# Addon-mapleCUx_HM-RFM69-V10-005.net
KiCad netlist of a schematic drawn in EAGLE
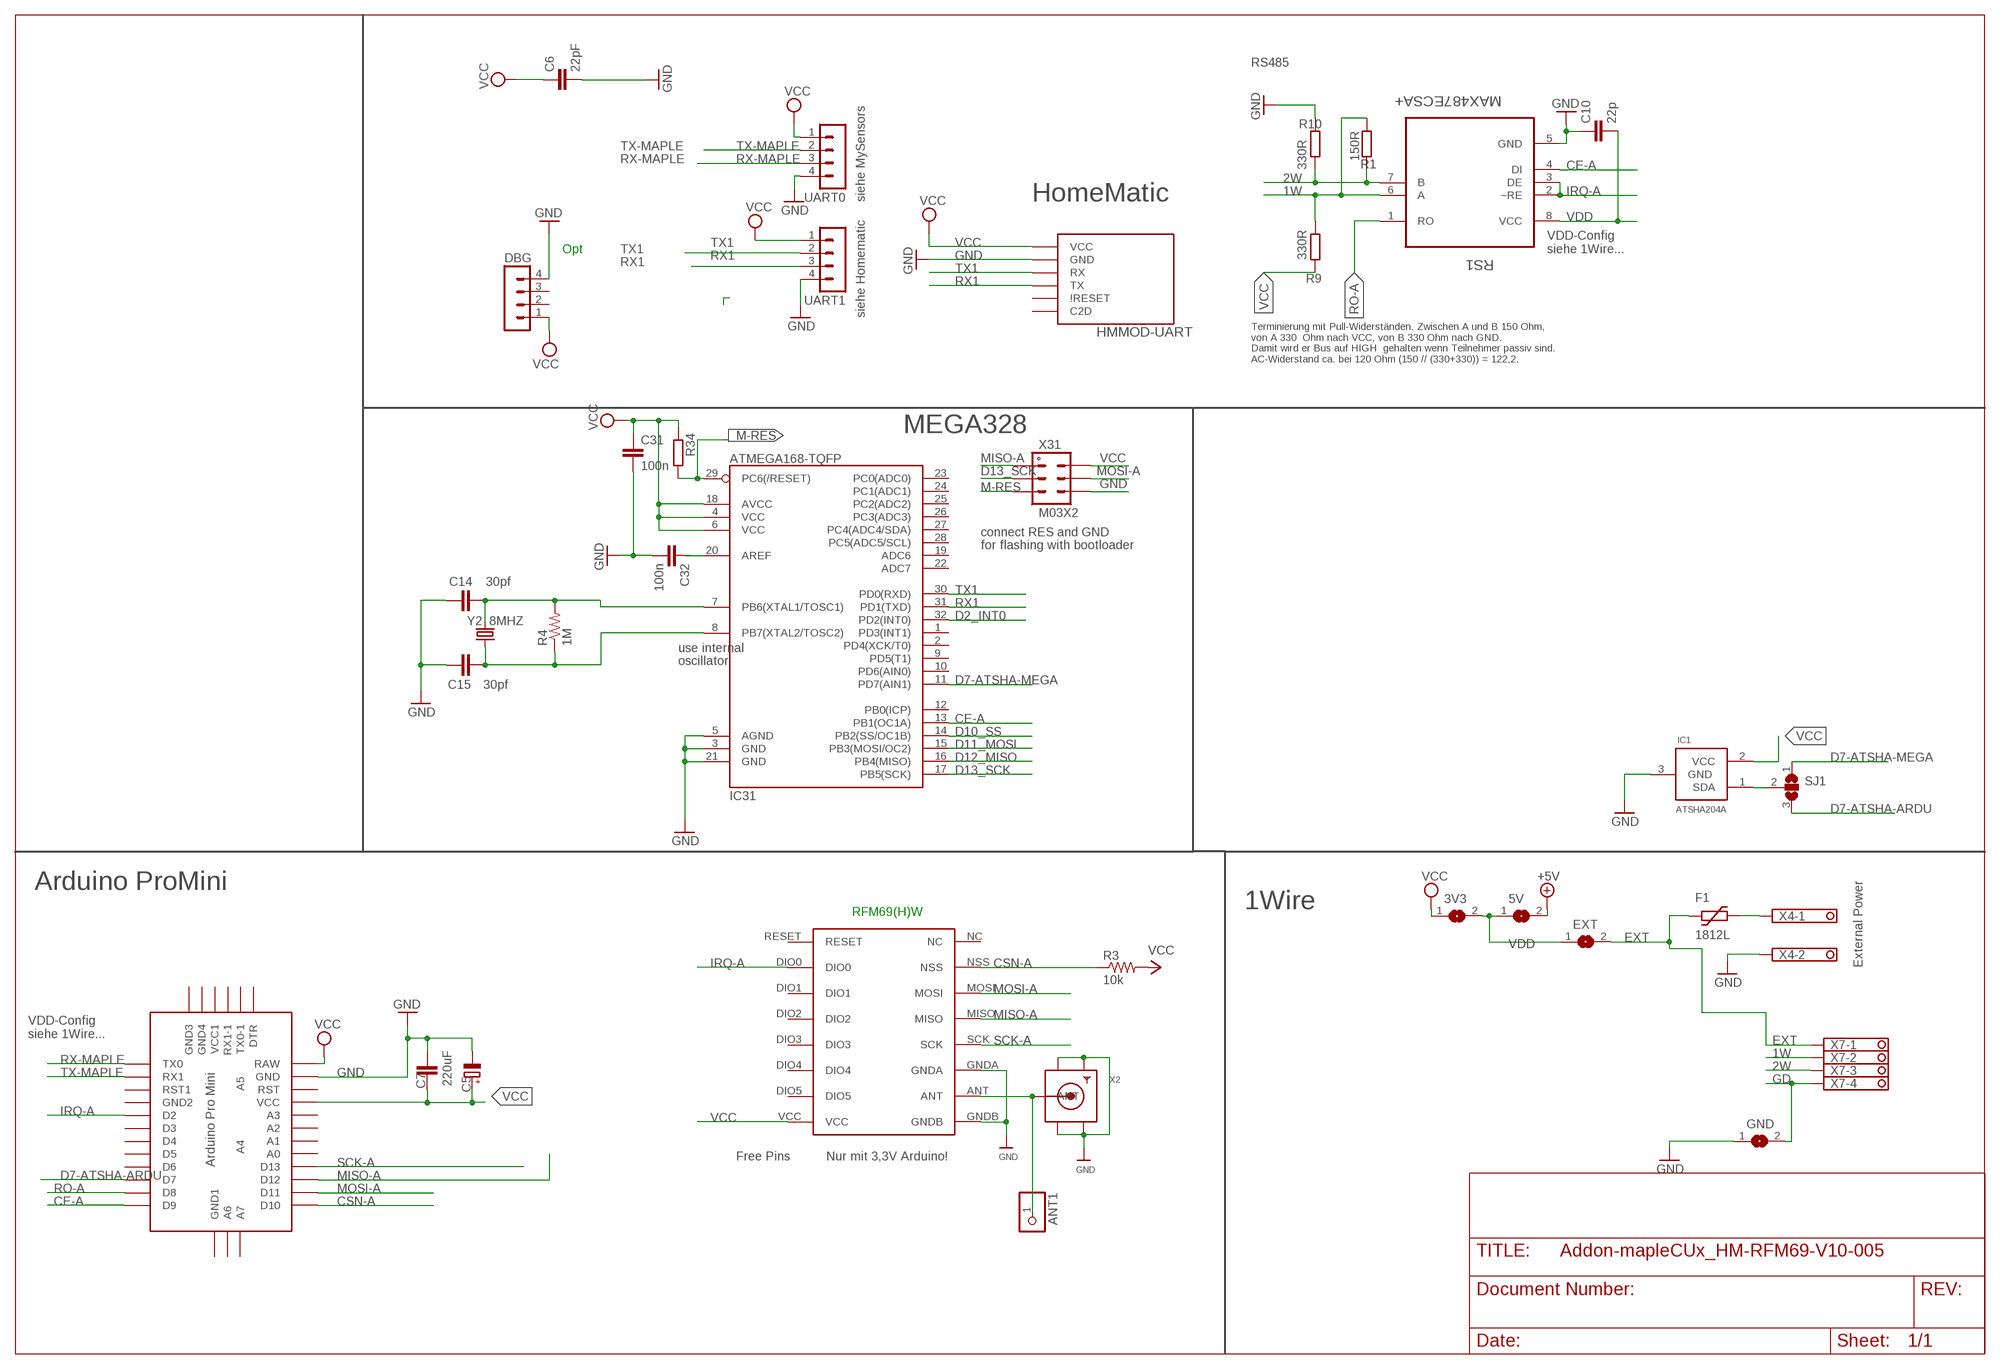
[diagram p0: schematic, sheet 1]

(export (version "E")
  (design (tool "Eeschema 10.0.6"))
  (components
    (comp (ref "3V3") (value "SJ") (footprint "eagle-import:SJ") (libsource (lib "eagle-import") (part "SJ")))
    (comp (ref "5V") (value "SJ") (footprint "eagle-import:SJ") (libsource (lib "eagle-import") (part "SJ")))
    (comp (ref "ANT1")
      (value "PINHD-1X1")
      (footprint "eagle-import:1X01")
      (libsource (lib "eagle-import") (part "PINHD-1X1"))
    )
    (comp (ref "C5")
      (value "220uF")
      (footprint "eagle-import:E5-8,5")
      (libsource (lib "eagle-import") (part "CPOL-EUE5-8.5"))
    )
    (comp (ref "C6")
      (value "22pF")
      (footprint "eagle-import:C0805")
      (libsource (lib "eagle-import") (part "C-EUC0805"))
    )
    (comp (ref "C7")
      (value "C-EUC1812")
      (footprint "eagle-import:C1812")
      (libsource (lib "eagle-import") (part "C-EUC1812"))
    )
    (comp (ref "C10")
      (value "22p")
      (footprint "eagle-import:C0805")
      (libsource (lib "eagle-import") (part "C-EUC0805"))
    )
    (comp (ref "C14")
      (value "30pf")
      (footprint "eagle-import:0805")
      (libsource (lib "eagle-import") (part "CAP0805"))
    )
    (comp (ref "C15")
      (value "30pf")
      (footprint "eagle-import:0805")
      (libsource (lib "eagle-import") (part "CAP0805"))
    )
    (comp (ref "C31")
      (value "100n")
      (footprint "eagle-import:C0805")
      (libsource (lib "eagle-import") (part "C-EUC0805"))
    )
    (comp (ref "C32")
      (value "100n")
      (footprint "eagle-import:C0805")
      (libsource (lib "eagle-import") (part "C-EUC0805"))
    )
    (comp (ref "DBG")
      (value "MA04-1")
      (footprint "eagle-import:MA04-1")
      (libsource (lib "eagle-import") (part "MA04-1"))
    )
    (comp (ref "EXT") (value "SJ") (footprint "eagle-import:SJ") (libsource (lib "eagle-import") (part "SJ")))
    (comp (ref "F1")
      (value "1812L")
      (footprint "eagle-import:1812L")
      (libsource (lib "eagle-import") (part "1812L"))
    )
    (comp (ref "GND") (value "SJ") (footprint "eagle-import:SJ") (libsource (lib "eagle-import") (part "SJ")))
    (comp (ref "HMMOD-UART")
      (value "HM-MOD-UARTDIL")
      (footprint "eagle-import:HM-MOD-UART-DIL")
      (libsource (lib "eagle-import") (part "HM-MOD-UARTDIL"))
    )
    (comp (ref "IC1")
      (value "ATSHA204A")
      (footprint "eagle-import:SOT23")
      (libsource (lib "eagle-import") (part "ATSHA204A"))
    )
    (comp (ref "IC31")
      (value "ATMEGA168-TQFP")
      (footprint "eagle-import:TQFP32-08")
      (libsource (lib "eagle-import") (part "ATMEGA168-TQFP"))
    )
    (comp (ref "R1")
      (value "150R")
      (footprint "eagle-import:R0805")
      (libsource (lib "eagle-import") (part "R-EU_R0805"))
    )
    (comp (ref "R3")
      (value "10k")
      (footprint "eagle-import:0805")
      (libsource (lib "eagle-import") (part "RESISTOR0805-RES"))
    )
    (comp (ref "R4")
      (value "1M")
      (footprint "eagle-import:0805")
      (libsource (lib "eagle-import") (part "RESISTOR0805-RES"))
    )
    (comp (ref "R9")
      (value "330R")
      (footprint "eagle-import:R0805")
      (libsource (lib "eagle-import") (part "R-EU_R0805"))
    )
    (comp (ref "R10")
      (value "330R")
      (footprint "eagle-import:R0805")
      (libsource (lib "eagle-import") (part "R-EU_R0805"))
    )
    (comp (ref "R34")
      (value "R-EU_R0805")
      (footprint "eagle-import:R0805")
      (libsource (lib "eagle-import") (part "R-EU_R0805"))
    )
    (comp (ref "RFM69W")
      (value "RFM69HW")
      (footprint "eagle-import:RFM")
      (libsource (lib "eagle-import") (part "RFM69HW"))
    )
    (comp (ref "RS1")
      (value "MAX487ECSA+")
      (footprint "eagle-import:SOIC127P600X175-8N")
      (libsource (lib "eagle-import") (part "MAX487ECSA+"))
    )
    (comp (ref "SJ1")
      (value "SJ2W")
      (footprint "eagle-import:SJ_2")
      (libsource (lib "eagle-import") (part "SJ2W"))
    )
    (comp (ref "U$2")
      (value "ABK-PRO-MINI")
      (footprint "eagle-import:ABK-PRO-MINI")
      (libsource (lib "eagle-import") (part "ABK-PRO-MINI"))
    )
    (comp (ref "UART0")
      (value "MA04-1")
      (footprint "eagle-import:MA04-1")
      (libsource (lib "eagle-import") (part "MA04-1"))
    )
    (comp (ref "UART1")
      (value "MA04-1")
      (footprint "eagle-import:MA04-1")
      (libsource (lib "eagle-import") (part "MA04-1"))
    )
    (comp (ref "X2")
      (value "SMACONNECTOR_EDGE")
      (footprint "eagle-import:SMA_EDGELAUNCH")
      (libsource (lib "eagle-import") (part "SMACONNECTOR_EDGE"))
    )
    (comp (ref "X4")
      (value "1751248")
      (footprint "eagle-import:1751248")
      (libsource (lib "eagle-import") (part "1751248"))
    )
    (comp (ref "X7")
      (value "1751264")
      (footprint "eagle-import:1751264")
      (libsource (lib "eagle-import") (part "1751264"))
    )
    (comp (ref "X31")
      (value "M03X2")
      (footprint "eagle-import:2X03-1.27MM_SMD")
      (libsource (lib "eagle-import") (part "M03X2"))
    )
    (comp (ref "Y2")
      (value "8MHZ")
      (footprint "eagle-import:CRYSTAL-TXC-7A")
      (libsource (lib "eagle-import") (part "CRYSTALTXC-7A"))
    )
  )
  (nets
    (net (code "1") (name "+5V") (class "Default")
      (node (ref "5V") (pin "2") (pinfunction "2_2") (pintype "passive"))
    )
    (net (code "2") (name "/1W") (class "Default")
      (node (ref "R1") (pin "1") (pinfunction "1_1") (pintype "passive"))
      (node (ref "R9") (pin "2") (pinfunction "2_2") (pintype "passive"))
      (node (ref "RS1") (pin "6") (pinfunction "A_6") (pintype "bidirectional"))
      (node (ref "X7") (pin "2") (pinfunction "K_2") (pintype "passive"))
    )
    (net (code "3") (name "/2W") (class "Default")
      (node (ref "R1") (pin "2") (pinfunction "2_2") (pintype "passive"))
      (node (ref "R10") (pin "1") (pinfunction "1_1") (pintype "passive"))
      (node (ref "RS1") (pin "7") (pinfunction "B_7") (pintype "bidirectional"))
      (node (ref "X7") (pin "3") (pinfunction "K_3") (pintype "passive"))
    )
    (net (code "4") (name "/CE-A") (class "Default")
      (node (ref "IC31") (pin "13") (pinfunction "PB1(OC1A)_13") (pintype "bidirectional"))
      (node (ref "RS1") (pin "4") (pinfunction "DI_4") (pintype "input"))
      (node (ref "U$2") (pin "D9") (pinfunction "D9_D9") (pintype "bidirectional"))
    )
    (net (code "5") (name "/CSN-A") (class "Default")
      (node (ref "R3") (pin "1") (pinfunction "1_1") (pintype "passive"))
      (node (ref "RFM69W") (pin "NSS") (pinfunction "NSS_NSS") (pintype "bidirectional"))
      (node (ref "U$2") (pin "D10") (pinfunction "D10_D10") (pintype "bidirectional"))
    )
    (net (code "6") (name "/D2_INT0") (class "Default")
      (node (ref "IC31") (pin "32") (pinfunction "PD2(INT0)_32") (pintype "bidirectional"))
    )
    (net (code "7") (name "/D7-ATSHA-ARDU") (class "Default")
      (node (ref "SJ1") (pin "3") (pinfunction "3_3") (pintype "passive"))
      (node (ref "U$2") (pin "D7") (pinfunction "D7_D7") (pintype "bidirectional"))
    )
    (net (code "8") (name "/D7-ATSHA-MEGA") (class "Default")
      (node (ref "IC31") (pin "11") (pinfunction "PD7(AIN1)_11") (pintype "bidirectional"))
      (node (ref "SJ1") (pin "1") (pinfunction "1_1") (pintype "passive"))
    )
    (net (code "9") (name "/D10_SS") (class "Default")
      (node (ref "IC31") (pin "14") (pinfunction "PB2(SS/OC1B)_14") (pintype "bidirectional"))
    )
    (net (code "10") (name "/D11_MOSI") (class "Default")
      (node (ref "IC31") (pin "15") (pinfunction "PB3(MOSI/OC2)_15") (pintype "bidirectional"))
    )
    (net (code "11") (name "/D12_MISO") (class "Default")
      (node (ref "IC31") (pin "16") (pinfunction "PB4(MISO)_16") (pintype "bidirectional"))
    )
    (net (code "12") (name "/D13_SCK") (class "Default")
      (node (ref "IC31") (pin "17") (pinfunction "PB5(SCK)_17") (pintype "bidirectional"))
      (node (ref "X31") (pin "P$3") (pinfunction "3_P$3") (pintype "passive"))
    )
    (net (code "13") (name "/EXT") (class "Default")
      (node (ref "EXT") (pin "2") (pinfunction "2_2") (pintype "passive"))
      (node (ref "F1") (pin "P$1") (pinfunction "1_P$1") (pintype "passive"))
      (node (ref "X7") (pin "1") (pinfunction "K_1") (pintype "passive"))
    )
    (net (code "14") (name "/GD") (class "Default")
      (node (ref "GND") (pin "2") (pinfunction "2_2") (pintype "passive"))
      (node (ref "X7") (pin "4") (pinfunction "K_4") (pintype "passive"))
    )
    (net (code "15") (name "/IRQ-A") (class "Default")
      (node (ref "RFM69W") (pin "DIO0") (pinfunction "DIO0_DIO0") (pintype "bidirectional"))
      (node (ref "RS1") (pin "2") (pinfunction "~{RE}_2") (pintype "input"))
      (node (ref "RS1") (pin "3") (pinfunction "DE_3") (pintype "input"))
      (node (ref "U$2") (pin "D2") (pinfunction "D2_D2") (pintype "bidirectional"))
    )
    (net (code "16") (name "/M-RES") (class "Default")
      (node (ref "IC31") (pin "29") (pinfunction "PC6(/RESET)_29") (pintype "bidirectional"))
      (node (ref "R34") (pin "2") (pinfunction "2_2") (pintype "passive"))
      (node (ref "X31") (pin "P$5") (pinfunction "5_P$5") (pintype "passive"))
    )
    (net (code "17") (name "/MISO-A") (class "Default")
      (node (ref "RFM69W") (pin "MISO") (pinfunction "MISO_MISO") (pintype "bidirectional"))
      (node (ref "U$2") (pin "D12") (pinfunction "D12_D12") (pintype "bidirectional"))
      (node (ref "X31") (pin "P$1") (pinfunction "1_P$1") (pintype "passive"))
    )
    (net (code "18") (name "/MOSI-A") (class "Default")
      (node (ref "RFM69W") (pin "MOSI") (pinfunction "MOSI_MOSI") (pintype "bidirectional"))
      (node (ref "U$2") (pin "D11") (pinfunction "D11_D11") (pintype "bidirectional"))
      (node (ref "X31") (pin "P$4") (pinfunction "4_P$4") (pintype "passive"))
    )
    (net (code "19") (name "/RX-MAPLE") (class "Default")
      (node (ref "U$2") (pin "TX0") (pinfunction "TX0_TX0") (pintype "bidirectional"))
      (node (ref "UART0") (pin "3") (pinfunction "3_3") (pintype "passive"))
    )
    (net (code "20") (name "/RX1") (class "Default")
      (node (ref "HMMOD-UART") (pin "5") (pinfunction "TX_5") (pintype "bidirectional"))
      (node (ref "IC31") (pin "31") (pinfunction "PD1(TXD)_31") (pintype "bidirectional"))
      (node (ref "UART1") (pin "3") (pinfunction "3_3") (pintype "passive"))
    )
    (net (code "21") (name "/SCK-A") (class "Default")
      (node (ref "RFM69W") (pin "SCK") (pinfunction "SCK_SCK") (pintype "bidirectional"))
      (node (ref "U$2") (pin "D13") (pinfunction "D13_D13") (pintype "bidirectional"))
    )
    (net (code "22") (name "/TX-MAPLE") (class "Default")
      (node (ref "U$2") (pin "RX1") (pinfunction "RX1_RX1") (pintype "bidirectional"))
      (node (ref "UART0") (pin "2") (pinfunction "2_2") (pintype "passive"))
    )
    (net (code "23") (name "/TX1") (class "Default")
      (node (ref "HMMOD-UART") (pin "6") (pinfunction "RX_6") (pintype "bidirectional"))
      (node (ref "IC31") (pin "30") (pinfunction "PD0(RXD)_30") (pintype "bidirectional"))
      (node (ref "UART1") (pin "2") (pinfunction "2_2") (pintype "passive"))
    )
    (net (code "24") (name "/VDD") (class "Default")
      (node (ref "3V3") (pin "2") (pinfunction "2_2") (pintype "passive"))
      (node (ref "5V") (pin "1") (pinfunction "1_1") (pintype "passive"))
      (node (ref "C10") (pin "2") (pinfunction "2_2") (pintype "passive"))
      (node (ref "EXT") (pin "1") (pinfunction "1_1") (pintype "passive"))
      (node (ref "RS1") (pin "8") (pinfunction "VCC_8") (pintype "power_in"))
    )
    (net (code "25") (name "GND") (class "Default")
      (node (ref "C10") (pin "1") (pinfunction "1_1") (pintype "passive"))
      (node (ref "C14") (pin "1") (pinfunction "1_1") (pintype "passive"))
      (node (ref "C15") (pin "1") (pinfunction "1_1") (pintype "passive"))
      (node (ref "C31") (pin "2") (pinfunction "2_2") (pintype "passive"))
      (node (ref "C32") (pin "2") (pinfunction "2_2") (pintype "passive"))
      (node (ref "C5") (pin "-") (pinfunction "-_-") (pintype "passive"))
      (node (ref "C6") (pin "2") (pinfunction "2_2") (pintype "passive"))
      (node (ref "C7") (pin "1") (pinfunction "1_1") (pintype "passive"))
      (node (ref "DBG") (pin "4") (pinfunction "4_4") (pintype "passive"))
      (node (ref "GND") (pin "1") (pinfunction "1_1") (pintype "passive"))
      (node (ref "HMMOD-UART") (pin "2") (pinfunction "GND_2") (pintype "power_in"))
      (node (ref "IC1") (pin "3") (pinfunction "GND_3") (pintype "bidirectional"))
      (node (ref "IC31") (pin "21") (pinfunction "GND_21") (pintype "bidirectional"))
      (node (ref "IC31") (pin "3") (pinfunction "GND_3") (pintype "bidirectional"))
      (node (ref "IC31") (pin "5") (pinfunction "AGND_5") (pintype "bidirectional"))
      (node (ref "R10") (pin "2") (pinfunction "2_2") (pintype "passive"))
      (node (ref "RFM69W") (pin "GNDA") (pinfunction "GNDA_GNDA") (pintype "bidirectional"))
      (node (ref "RFM69W") (pin "GNDB") (pinfunction "GNDB_GNDB") (pintype "bidirectional"))
      (node (ref "RS1") (pin "5") (pinfunction "GND_5") (pintype "passive"))
      (node (ref "U$2") (pin "GND") (pinfunction "GND_GND") (pintype "bidirectional"))
      (node (ref "UART0") (pin "4") (pinfunction "4_4") (pintype "passive"))
      (node (ref "UART1") (pin "4") (pinfunction "4_4") (pintype "passive"))
      (node (ref "X2") (pin "GND@1") (pinfunction "GND4_GND@1") (pintype "power_in"))
      (node (ref "X2") (pin "GND@2") (pinfunction "GND3_GND@2") (pintype "power_in"))
      (node (ref "X2") (pin "GND@3") (pinfunction "GND2_GND@3") (pintype "power_in"))
      (node (ref "X2") (pin "GND@4") (pinfunction "GND1_GND@4") (pintype "power_in"))
      (node (ref "X31") (pin "P$6") (pinfunction "6_P$6") (pintype "passive"))
      (node (ref "X4") (pin "2") (pinfunction "K_2") (pintype "passive"))
    )
    (net (code "26") (name "Net-(F1-2)") (class "Default")
      (node (ref "F1") (pin "P$2") (pinfunction "2_P$2") (pintype "passive"))
      (node (ref "X4") (pin "1") (pinfunction "K_1") (pintype "passive"))
    )
    (net (code "27") (name "Net-(IC1-SDA)") (class "Default")
      (node (ref "IC1") (pin "1") (pinfunction "SDA_1") (pintype "bidirectional"))
      (node (ref "SJ1") (pin "2") (pinfunction "2_2") (pintype "passive"))
    )
    (net (code "28") (name "Net-(IC31-AREF)") (class "Default")
      (node (ref "C32") (pin "1") (pinfunction "1_1") (pintype "passive"))
      (node (ref "IC31") (pin "20") (pinfunction "AREF_20") (pintype "bidirectional"))
    )
    (net (code "29") (name "Net-(IC31-PB6(XTAL1{slash}TOSC1))") (class "Default")
      (node (ref "C14") (pin "2") (pinfunction "2_2") (pintype "passive"))
      (node (ref "IC31") (pin "7") (pinfunction "PB6(XTAL1/TOSC1)_7") (pintype "bidirectional"))
      (node (ref "R4") (pin "2") (pinfunction "2_2") (pintype "passive"))
      (node (ref "Y2") (pin "P$2") (pinfunction "2_P$2") (pintype "passive"))
    )
    (net (code "30") (name "Net-(IC31-PB7(XTAL2{slash}TOSC2))") (class "Default")
      (node (ref "C15") (pin "2") (pinfunction "2_2") (pintype "passive"))
      (node (ref "IC31") (pin "8") (pinfunction "PB7(XTAL2/TOSC2)_8") (pintype "bidirectional"))
      (node (ref "R4") (pin "1") (pinfunction "1_1") (pintype "passive"))
      (node (ref "Y2") (pin "P$1") (pinfunction "1_P$1") (pintype "passive"))
    )
    (net (code "31") (name "Net-(X2-ANT)") (class "Default")
      (node (ref "ANT1") (pin "1") (pinfunction "1_1") (pintype "passive"))
      (node (ref "RFM69W") (pin "ANT") (pinfunction "ANT_ANT") (pintype "bidirectional"))
      (node (ref "X2") (pin "P") (pinfunction "ANT_P") (pintype "bidirectional"))
    )
    (net (code "32") (name "RO-A") (class "Default")
      (node (ref "RS1") (pin "1") (pinfunction "RO_1") (pintype "output"))
      (node (ref "U$2") (pin "D8") (pinfunction "D8_D8") (pintype "bidirectional"))
    )
    (net (code "33") (name "VCC") (class "Default")
      (node (ref "3V3") (pin "1") (pinfunction "1_1") (pintype "passive"))
      (node (ref "C31") (pin "1") (pinfunction "1_1") (pintype "passive"))
      (node (ref "C5") (pin "+") (pinfunction "+_+") (pintype "passive"))
      (node (ref "C6") (pin "1") (pinfunction "1_1") (pintype "passive"))
      (node (ref "C7") (pin "2") (pinfunction "2_2") (pintype "passive"))
      (node (ref "DBG") (pin "1") (pinfunction "1_1") (pintype "passive"))
      (node (ref "HMMOD-UART") (pin "1") (pinfunction "VCC_1") (pintype "power_in"))
      (node (ref "IC1") (pin "2") (pinfunction "VCC_2") (pintype "bidirectional"))
      (node (ref "IC31") (pin "18") (pinfunction "AVCC_18") (pintype "bidirectional"))
      (node (ref "IC31") (pin "4") (pinfunction "VCC_4") (pintype "bidirectional"))
      (node (ref "IC31") (pin "6") (pinfunction "VCC_6") (pintype "bidirectional"))
      (node (ref "R3") (pin "2") (pinfunction "2_2") (pintype "passive"))
      (node (ref "R34") (pin "1") (pinfunction "1_1") (pintype "passive"))
      (node (ref "R9") (pin "1") (pinfunction "1_1") (pintype "passive"))
      (node (ref "RFM69W") (pin "VCC") (pinfunction "VCC_VCC") (pintype "bidirectional"))
      (node (ref "U$2") (pin "RAW") (pinfunction "RAW_RAW") (pintype "bidirectional"))
      (node (ref "U$2") (pin "VCC") (pinfunction "VCC_VCC") (pintype "bidirectional"))
      (node (ref "UART0") (pin "1") (pinfunction "1_1") (pintype "passive"))
      (node (ref "UART1") (pin "1") (pinfunction "1_1") (pintype "passive"))
      (node (ref "X31") (pin "P$2") (pinfunction "2_P$2") (pintype "passive"))
    )
    (net (code "34") (name "unconnected-(DBG-Pad2)") (class "Default")
      (node (ref "DBG") (pin "2") (pinfunction "2_2") (pintype "passive"))
    )
    (net (code "35") (name "unconnected-(DBG-Pad3)") (class "Default")
      (node (ref "DBG") (pin "3") (pinfunction "3_3") (pintype "passive"))
    )
    (net (code "36") (name "unconnected-(HMMOD-UART-C2D-Pad3)") (class "Default")
      (node (ref "HMMOD-UART") (pin "3") (pinfunction "C2D_3") (pintype "bidirectional"))
    )
    (net (code "37") (name "unconnected-(HMMOD-UART-\\~{RESET}-Pad4)") (class "Default")
      (node (ref "HMMOD-UART") (pin "4") (pinfunction "\\~{RESET}_4") (pintype "bidirectional"))
    )
    (net (code "38") (name "unconnected-(IC31-ADC6-Pad19)") (class "Default")
      (node (ref "IC31") (pin "19") (pinfunction "ADC6_19") (pintype "bidirectional"))
    )
    (net (code "39") (name "unconnected-(IC31-ADC7-Pad22)") (class "Default")
      (node (ref "IC31") (pin "22") (pinfunction "ADC7_22") (pintype "bidirectional"))
    )
    (net (code "40") (name "unconnected-(IC31-PB0(ICP)-Pad12)") (class "Default")
      (node (ref "IC31") (pin "12") (pinfunction "PB0(ICP)_12") (pintype "bidirectional"))
    )
    (net (code "41") (name "unconnected-(IC31-PC0(ADC0)-Pad23)") (class "Default")
      (node (ref "IC31") (pin "23") (pinfunction "PC0(ADC0)_23") (pintype "bidirectional"))
    )
    (net (code "42") (name "unconnected-(IC31-PC1(ADC1)-Pad24)") (class "Default")
      (node (ref "IC31") (pin "24") (pinfunction "PC1(ADC1)_24") (pintype "bidirectional"))
    )
    (net (code "43") (name "unconnected-(IC31-PC2(ADC2)-Pad25)") (class "Default")
      (node (ref "IC31") (pin "25") (pinfunction "PC2(ADC2)_25") (pintype "bidirectional"))
    )
    (net (code "44") (name "unconnected-(IC31-PC3(ADC3)-Pad26)") (class "Default")
      (node (ref "IC31") (pin "26") (pinfunction "PC3(ADC3)_26") (pintype "bidirectional"))
    )
    (net (code "45") (name "unconnected-(IC31-PC4(ADC4{slash}SDA)-Pad27)") (class "Default")
      (node (ref "IC31") (pin "27") (pinfunction "PC4(ADC4/SDA)_27") (pintype "bidirectional"))
    )
    (net (code "46") (name "unconnected-(IC31-PC5(ADC5{slash}SCL)-Pad28)") (class "Default")
      (node (ref "IC31") (pin "28") (pinfunction "PC5(ADC5/SCL)_28") (pintype "bidirectional"))
    )
    (net (code "47") (name "unconnected-(IC31-PD3(INT1)-Pad1)") (class "Default")
      (node (ref "IC31") (pin "1") (pinfunction "PD3(INT1)_1") (pintype "bidirectional"))
    )
    (net (code "48") (name "unconnected-(IC31-PD4(XCK{slash}T0)-Pad2)") (class "Default")
      (node (ref "IC31") (pin "2") (pinfunction "PD4(XCK/T0)_2") (pintype "bidirectional"))
    )
    (net (code "49") (name "unconnected-(IC31-PD5(T1)-Pad9)") (class "Default")
      (node (ref "IC31") (pin "9") (pinfunction "PD5(T1)_9") (pintype "bidirectional"))
    )
    (net (code "50") (name "unconnected-(IC31-PD6(AIN0)-Pad10)") (class "Default")
      (node (ref "IC31") (pin "10") (pinfunction "PD6(AIN0)_10") (pintype "bidirectional"))
    )
    (net (code "51") (name "unconnected-(RFM69W-PadDIO1)") (class "Default")
      (node (ref "RFM69W") (pin "DIO1") (pinfunction "DIO1_DIO1") (pintype "bidirectional"))
    )
    (net (code "52") (name "unconnected-(RFM69W-PadDIO2)") (class "Default")
      (node (ref "RFM69W") (pin "DIO2") (pinfunction "DIO2_DIO2") (pintype "bidirectional"))
    )
    (net (code "53") (name "unconnected-(RFM69W-PadDIO3)") (class "Default")
      (node (ref "RFM69W") (pin "DIO3") (pinfunction "DIO3_DIO3") (pintype "bidirectional"))
    )
    (net (code "54") (name "unconnected-(RFM69W-PadDIO4)") (class "Default")
      (node (ref "RFM69W") (pin "DIO4") (pinfunction "DIO4_DIO4") (pintype "bidirectional"))
    )
    (net (code "55") (name "unconnected-(RFM69W-PadDIO5)") (class "Default")
      (node (ref "RFM69W") (pin "DIO5") (pinfunction "DIO5_DIO5") (pintype "bidirectional"))
    )
    (net (code "56") (name "unconnected-(RFM69W-PadNC)") (class "Default")
      (node (ref "RFM69W") (pin "NC") (pinfunction "NC_NC") (pintype "bidirectional"))
    )
    (net (code "57") (name "unconnected-(RFM69W-PadRESET)") (class "Default")
      (node (ref "RFM69W") (pin "RESET") (pinfunction "RESET_RESET") (pintype "bidirectional"))
    )
    (net (code "58") (name "unconnected-(U$2-GND1-PadGND4)") (class "Default")
      (node (ref "U$2") (pin "GND4") (pinfunction "GND1_GND4") (pintype "bidirectional"))
    )
    (net (code "59") (name "unconnected-(U$2-GND2-PadGND1)") (class "Default")
      (node (ref "U$2") (pin "GND1") (pinfunction "GND2_GND1") (pintype "bidirectional"))
    )
    (net (code "60") (name "unconnected-(U$2-GND3-PadGND2)") (class "Default")
      (node (ref "U$2") (pin "GND2") (pinfunction "GND3_GND2") (pintype "bidirectional"))
    )
    (net (code "61") (name "unconnected-(U$2-GND4-PadGND3)") (class "Default")
      (node (ref "U$2") (pin "GND3") (pinfunction "GND4_GND3") (pintype "bidirectional"))
    )
    (net (code "62") (name "unconnected-(U$2-PadA0)") (class "Default")
      (node (ref "U$2") (pin "A0") (pinfunction "A0_A0") (pintype "bidirectional"))
    )
    (net (code "63") (name "unconnected-(U$2-PadA1)") (class "Default")
      (node (ref "U$2") (pin "A1") (pinfunction "A1_A1") (pintype "bidirectional"))
    )
    (net (code "64") (name "unconnected-(U$2-PadA2)") (class "Default")
      (node (ref "U$2") (pin "A2") (pinfunction "A2_A2") (pintype "bidirectional"))
    )
    (net (code "65") (name "unconnected-(U$2-PadA3)") (class "Default")
      (node (ref "U$2") (pin "A3") (pinfunction "A3_A3") (pintype "bidirectional"))
    )
    (net (code "66") (name "unconnected-(U$2-PadA4)") (class "Default")
      (node (ref "U$2") (pin "A4") (pinfunction "A4_A4") (pintype "bidirectional"))
    )
    (net (code "67") (name "unconnected-(U$2-PadA5)") (class "Default")
      (node (ref "U$2") (pin "A5") (pinfunction "A5_A5") (pintype "bidirectional"))
    )
    (net (code "68") (name "unconnected-(U$2-PadA6)") (class "Default")
      (node (ref "U$2") (pin "A6") (pinfunction "A6_A6") (pintype "bidirectional"))
    )
    (net (code "69") (name "unconnected-(U$2-PadA7)") (class "Default")
      (node (ref "U$2") (pin "A7") (pinfunction "A7_A7") (pintype "bidirectional"))
    )
    (net (code "70") (name "unconnected-(U$2-PadD3)") (class "Default")
      (node (ref "U$2") (pin "D3") (pinfunction "D3_D3") (pintype "bidirectional"))
    )
    (net (code "71") (name "unconnected-(U$2-PadD4)") (class "Default")
      (node (ref "U$2") (pin "D4") (pinfunction "D4_D4") (pintype "bidirectional"))
    )
    (net (code "72") (name "unconnected-(U$2-PadD5)") (class "Default")
      (node (ref "U$2") (pin "D5") (pinfunction "D5_D5") (pintype "bidirectional"))
    )
    (net (code "73") (name "unconnected-(U$2-PadD6)") (class "Default")
      (node (ref "U$2") (pin "D6") (pinfunction "D6_D6") (pintype "bidirectional"))
    )
    (net (code "74") (name "unconnected-(U$2-PadDTR)") (class "Default")
      (node (ref "U$2") (pin "DTR") (pinfunction "DTR_DTR") (pintype "bidirectional"))
    )
    (net (code "75") (name "unconnected-(U$2-PadRST)") (class "Default")
      (node (ref "U$2") (pin "RST") (pinfunction "RST_RST") (pintype "bidirectional"))
    )
    (net (code "76") (name "unconnected-(U$2-PadRST1)") (class "Default")
      (node (ref "U$2") (pin "RST1") (pinfunction "RST1_RST1") (pintype "bidirectional"))
    )
    (net (code "77") (name "unconnected-(U$2-PadRX1-1)") (class "Default")
      (node (ref "U$2") (pin "RX1-1") (pinfunction "RX1-1_RX1-1") (pintype "bidirectional"))
    )
    (net (code "78") (name "unconnected-(U$2-PadTX0-1)") (class "Default")
      (node (ref "U$2") (pin "TX0-1") (pinfunction "TX0-1_TX0-1") (pintype "bidirectional"))
    )
    (net (code "79") (name "unconnected-(U$2-PadVCC1)") (class "Default")
      (node (ref "U$2") (pin "VCC1") (pinfunction "VCC1_VCC1") (pintype "bidirectional"))
    )
  )
)
